# Programming_main.net
KiCad netlist of a schematic drawn in Altium Designer
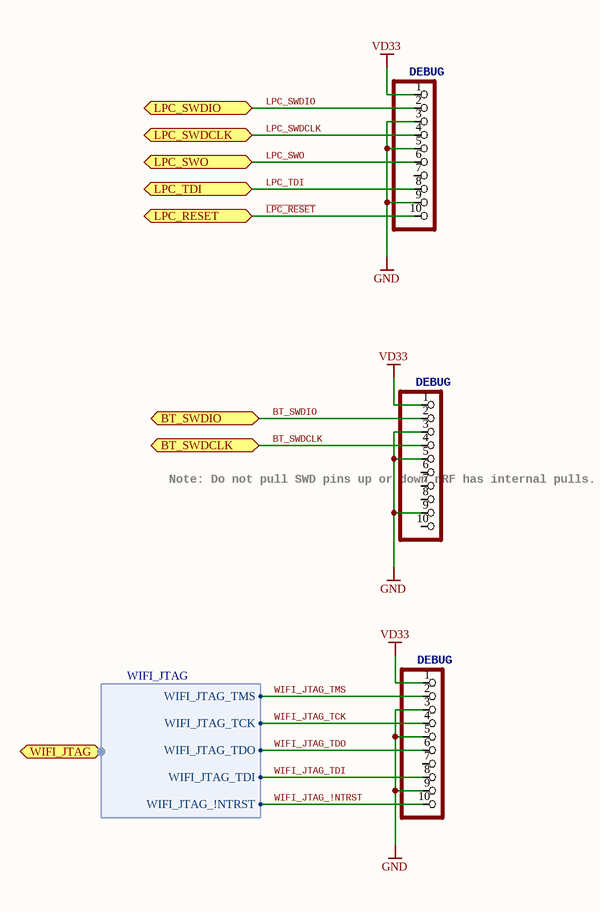
[diagram p0: Programming_main.SchDoc]

(export (version "E")
  (design (tool "Eeschema 10.0.6"))
  (components
    (comp (ref "LPC_DEBUG")
      (value "DEBUG")
      (footprint "2X05_SMT")
      (description "cortex DEBUG connector")
      (libsource (lib "WunderBar_v101") (part "HEADER-2X5SMD-1.27MM"))
    )
    (comp (ref "NRF_DEBUG")
      (value "DEBUG")
      (footprint "2X05_SMT")
      (description "cortex DEBUG connector")
      (libsource (lib "WunderBar_v101") (part "HEADER-2X5SMD-1.27MM"))
    )
    (comp (ref "WIFI_DEBUG")
      (value "DEBUG")
      (footprint "2X05_SMT")
      (description "cortex DEBUG connector")
      (libsource (lib "WunderBar_v101") (part "HEADER-2X5SMD-1.27MM"))
    )
  )
  (nets
    (net (code "2") (name "/BT_SWDCLK") (class "Default")
      (node (ref "NRF_DEBUG") (pin "4") (pinfunction "4_4") (pintype "passive"))
    )
    (net (code "3") (name "/BT_SWDIO") (class "Default")
      (node (ref "NRF_DEBUG") (pin "2") (pinfunction "2_2") (pintype "passive"))
    )
    (net (code "4") (name "/LPC_SWDCLK") (class "Default")
      (node (ref "LPC_DEBUG") (pin "4") (pinfunction "4_4") (pintype "passive"))
    )
    (net (code "5") (name "/LPC_SWDIO") (class "Default")
      (node (ref "LPC_DEBUG") (pin "2") (pinfunction "2_2") (pintype "passive"))
    )
    (net (code "6") (name "/LPC_SWO") (class "Default")
      (node (ref "LPC_DEBUG") (pin "6") (pinfunction "6_6") (pintype "passive"))
    )
    (net (code "7") (name "/LPC_TDI") (class "Default")
      (node (ref "LPC_DEBUG") (pin "8") (pinfunction "8_8") (pintype "passive"))
    )
    (net (code "8") (name "/WIFI_JTAG_!NTRST") (class "Default")
      (node (ref "WIFI_DEBUG") (pin "10") (pinfunction "10_10") (pintype "passive"))
    )
    (net (code "9") (name "/WIFI_JTAG_TCK") (class "Default")
      (node (ref "WIFI_DEBUG") (pin "4") (pinfunction "4_4") (pintype "passive"))
    )
    (net (code "10") (name "/WIFI_JTAG_TDI") (class "Default")
      (node (ref "WIFI_DEBUG") (pin "8") (pinfunction "8_8") (pintype "passive"))
    )
    (net (code "11") (name "/WIFI_JTAG_TDO") (class "Default")
      (node (ref "WIFI_DEBUG") (pin "6") (pinfunction "6_6") (pintype "passive"))
    )
    (net (code "12") (name "/WIFI_JTAG_TMS") (class "Default")
      (node (ref "WIFI_DEBUG") (pin "2") (pinfunction "2_2") (pintype "passive"))
    )
    (net (code "14") (name "/~{LPC_RESET}") (class "Default")
      (node (ref "LPC_DEBUG") (pin "10") (pinfunction "10_10") (pintype "passive"))
    )
    (net (code "15") (name "GND") (class "Default")
      (node (ref "LPC_DEBUG") (pin "3") (pinfunction "3_3") (pintype "passive"))
      (node (ref "LPC_DEBUG") (pin "5") (pinfunction "5_5") (pintype "passive"))
      (node (ref "LPC_DEBUG") (pin "9") (pinfunction "9_9") (pintype "passive"))
      (node (ref "NRF_DEBUG") (pin "3") (pinfunction "3_3") (pintype "passive"))
      (node (ref "NRF_DEBUG") (pin "5") (pinfunction "5_5") (pintype "passive"))
      (node (ref "NRF_DEBUG") (pin "9") (pinfunction "9_9") (pintype "passive"))
      (node (ref "WIFI_DEBUG") (pin "3") (pinfunction "3_3") (pintype "passive"))
      (node (ref "WIFI_DEBUG") (pin "5") (pinfunction "5_5") (pintype "passive"))
      (node (ref "WIFI_DEBUG") (pin "9") (pinfunction "9_9") (pintype "passive"))
    )
    (net (code "16") (name "VD33") (class "Default")
      (node (ref "LPC_DEBUG") (pin "1") (pinfunction "1_1") (pintype "passive"))
      (node (ref "NRF_DEBUG") (pin "1") (pinfunction "1_1") (pintype "passive"))
      (node (ref "WIFI_DEBUG") (pin "1") (pinfunction "1_1") (pintype "passive"))
    )
    (net (code "17") (name "unconnected-(LPC_DEBUG-Pad7)") (class "Default")
      (node (ref "LPC_DEBUG") (pin "7") (pinfunction "7_7") (pintype "passive"))
    )
    (net (code "18") (name "unconnected-(NRF_DEBUG-Pad6)") (class "Default")
      (node (ref "NRF_DEBUG") (pin "6") (pinfunction "6_6") (pintype "passive"))
    )
    (net (code "19") (name "unconnected-(NRF_DEBUG-Pad7)") (class "Default")
      (node (ref "NRF_DEBUG") (pin "7") (pinfunction "7_7") (pintype "passive"))
    )
    (net (code "20") (name "unconnected-(NRF_DEBUG-Pad8)") (class "Default")
      (node (ref "NRF_DEBUG") (pin "8") (pinfunction "8_8") (pintype "passive"))
    )
    (net (code "21") (name "unconnected-(NRF_DEBUG-Pad10)") (class "Default")
      (node (ref "NRF_DEBUG") (pin "10") (pinfunction "10_10") (pintype "passive"))
    )
    (net (code "22") (name "unconnected-(WIFI_DEBUG-Pad7)") (class "Default")
      (node (ref "WIFI_DEBUG") (pin "7") (pinfunction "7_7") (pintype "passive"))
    )
  )
)
